# power.net
KiCad netlist of a schematic drawn in Altium Designer
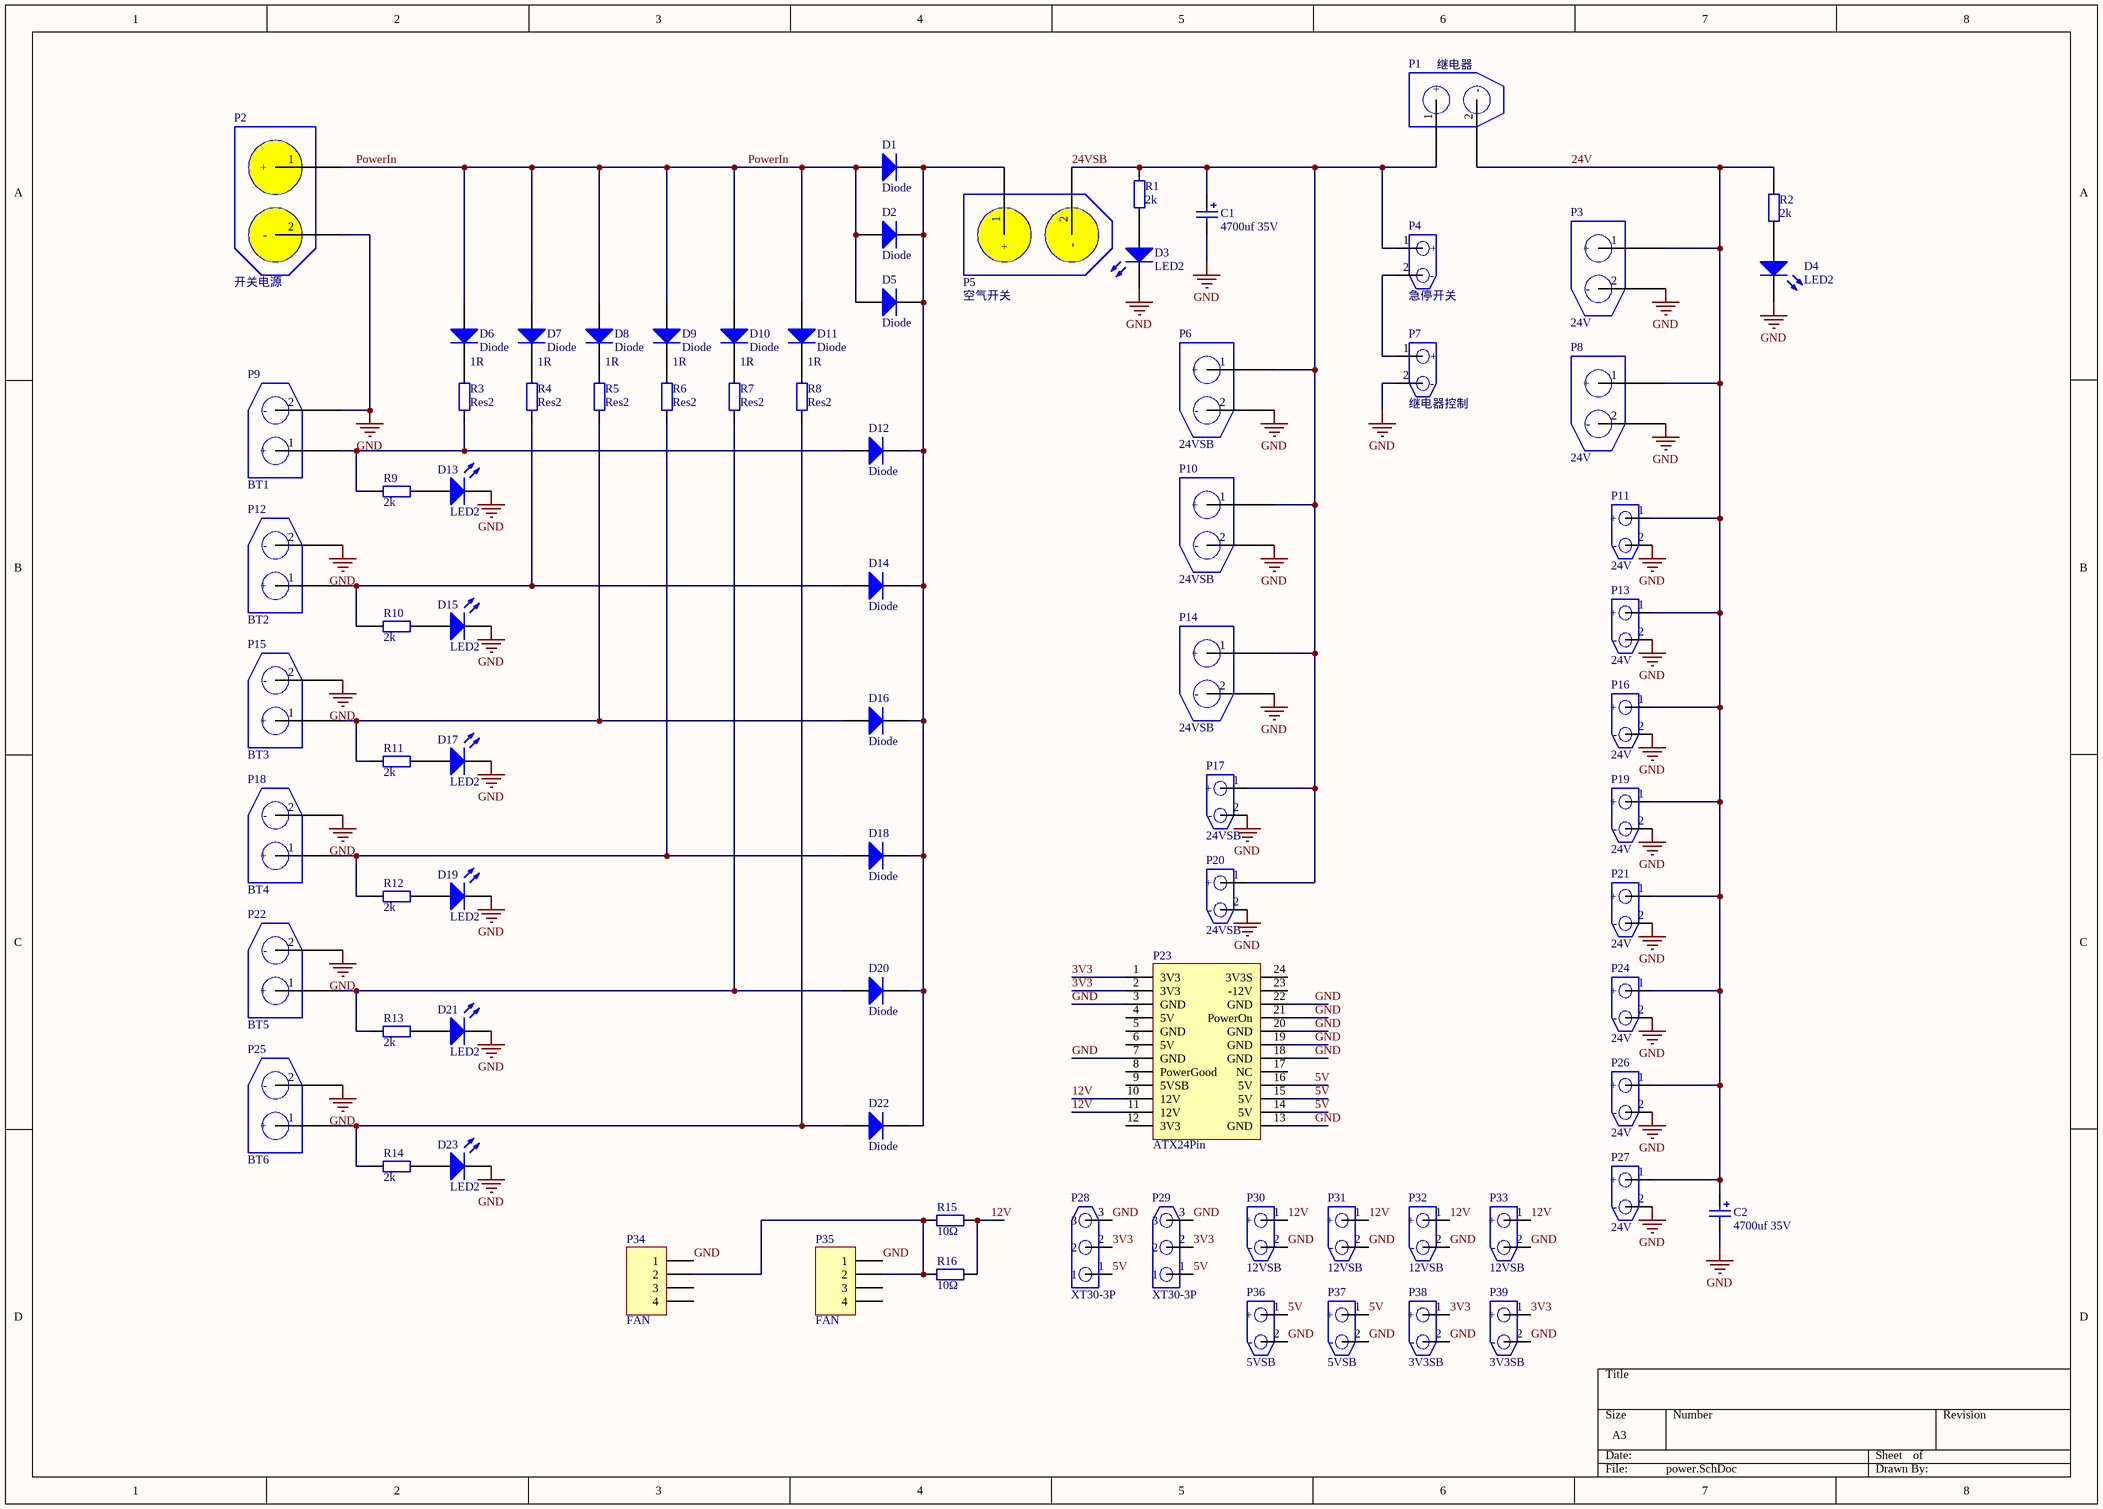
[diagram p0: power.SchDoc]

(export (version "E")
  (design (tool "Eeschema 10.0.6"))
  (components
    (comp (ref "C1")
      (value "4700uf 35V")
      (footprint "C1675")
      (description "Polarized Capacitor (Axial)")
      (fields (field (name "Comment") "Cap Pol2") (field (name "PUBLISHER") "Altium Limited"))
      (libsource (lib "Miscellaneous Devices") (part "Cap Pol2"))
    )
    (comp (ref "C2")
      (value "4700uf 35V")
      (footprint "C1675")
      (description "Polarized Capacitor (Axial)")
      (fields (field (name "Comment") "Cap Pol2") (field (name "PUBLISHER") "Altium Limited"))
      (libsource (lib "Miscellaneous Devices") (part "Cap Pol2"))
    )
    (comp (ref "D1")
      (value "Diode")
      (footprint "TO-247-2-S")
      (description "Default Diode")
      (fields (field (name "PUBLISHER") "Altium Limited"))
      (libsource (lib "Miscellaneous Devices") (part "Diode"))
    )
    (comp (ref "D2")
      (value "Diode")
      (footprint "TO-247-2-S")
      (description "Default Diode")
      (fields (field (name "PUBLISHER") "Altium Limited"))
      (libsource (lib "Miscellaneous Devices") (part "Diode"))
    )
    (comp (ref "D3")
      (value "LED2")
      (footprint "1608[0603]big")
      (description "Typical RED, GREEN, YELLOW, AMBER GaAs LED")
      (fields (field (name "PUBLISHER") "Altium Limited"))
      (libsource (lib "Miscellaneous Devices") (part "LED2"))
    )
    (comp (ref "D4")
      (value "LED2")
      (footprint "1608[0603]big")
      (description "Typical RED, GREEN, YELLOW, AMBER GaAs LED")
      (fields (field (name "PUBLISHER") "Altium Limited"))
      (libsource (lib "Miscellaneous Devices") (part "LED2"))
    )
    (comp (ref "D5")
      (value "Diode")
      (footprint "TO-247-2-S")
      (description "Default Diode")
      (fields (field (name "PUBLISHER") "Altium Limited"))
      (libsource (lib "Miscellaneous Devices") (part "Diode"))
    )
    (comp (ref "D6")
      (value "Diode")
      (footprint "TO-263")
      (description "Default Diode")
      (fields (field (name "PUBLISHER") "Altium Limited"))
      (libsource (lib "Miscellaneous Devices") (part "Diode"))
    )
    (comp (ref "D7")
      (value "Diode")
      (footprint "TO-263")
      (description "Default Diode")
      (fields (field (name "PUBLISHER") "Altium Limited"))
      (libsource (lib "Miscellaneous Devices") (part "Diode"))
    )
    (comp (ref "D8")
      (value "Diode")
      (footprint "TO-263")
      (description "Default Diode")
      (fields (field (name "PUBLISHER") "Altium Limited"))
      (libsource (lib "Miscellaneous Devices") (part "Diode"))
    )
    (comp (ref "D9")
      (value "Diode")
      (footprint "TO-263")
      (description "Default Diode")
      (fields (field (name "PUBLISHER") "Altium Limited"))
      (libsource (lib "Miscellaneous Devices") (part "Diode"))
    )
    (comp (ref "D10")
      (value "Diode")
      (footprint "TO-263")
      (description "Default Diode")
      (fields (field (name "PUBLISHER") "Altium Limited"))
      (libsource (lib "Miscellaneous Devices") (part "Diode"))
    )
    (comp (ref "D11")
      (value "Diode")
      (footprint "TO-263")
      (description "Default Diode")
      (fields (field (name "PUBLISHER") "Altium Limited"))
      (libsource (lib "Miscellaneous Devices") (part "Diode"))
    )
    (comp (ref "D12")
      (value "Diode")
      (footprint "TO-247-2-S")
      (description "Default Diode")
      (fields (field (name "PUBLISHER") "Altium Limited"))
      (libsource (lib "Miscellaneous Devices") (part "Diode"))
    )
    (comp (ref "D13")
      (value "LED2")
      (footprint "1608[0603]big")
      (description "Typical RED, GREEN, YELLOW, AMBER GaAs LED")
      (fields (field (name "PUBLISHER") "Altium Limited"))
      (libsource (lib "Miscellaneous Devices") (part "LED2"))
    )
    (comp (ref "D14")
      (value "Diode")
      (footprint "TO-247-2-S")
      (description "Default Diode")
      (fields (field (name "PUBLISHER") "Altium Limited"))
      (libsource (lib "Miscellaneous Devices") (part "Diode"))
    )
    (comp (ref "D15")
      (value "LED2")
      (footprint "1608[0603]big")
      (description "Typical RED, GREEN, YELLOW, AMBER GaAs LED")
      (fields (field (name "PUBLISHER") "Altium Limited"))
      (libsource (lib "Miscellaneous Devices") (part "LED2"))
    )
    (comp (ref "D16")
      (value "Diode")
      (footprint "TO-247-2-S")
      (description "Default Diode")
      (fields (field (name "PUBLISHER") "Altium Limited"))
      (libsource (lib "Miscellaneous Devices") (part "Diode"))
    )
    (comp (ref "D17")
      (value "LED2")
      (footprint "1608[0603]big")
      (description "Typical RED, GREEN, YELLOW, AMBER GaAs LED")
      (fields (field (name "PUBLISHER") "Altium Limited"))
      (libsource (lib "Miscellaneous Devices") (part "LED2"))
    )
    (comp (ref "D18")
      (value "Diode")
      (footprint "TO-247-2-S")
      (description "Default Diode")
      (fields (field (name "PUBLISHER") "Altium Limited"))
      (libsource (lib "Miscellaneous Devices") (part "Diode"))
    )
    (comp (ref "D19")
      (value "LED2")
      (footprint "1608[0603]big")
      (description "Typical RED, GREEN, YELLOW, AMBER GaAs LED")
      (fields (field (name "PUBLISHER") "Altium Limited"))
      (libsource (lib "Miscellaneous Devices") (part "LED2"))
    )
    (comp (ref "D20")
      (value "Diode")
      (footprint "TO-247-2-S")
      (description "Default Diode")
      (fields (field (name "PUBLISHER") "Altium Limited"))
      (libsource (lib "Miscellaneous Devices") (part "Diode"))
    )
    (comp (ref "D21")
      (value "LED2")
      (footprint "1608[0603]big")
      (description "Typical RED, GREEN, YELLOW, AMBER GaAs LED")
      (fields (field (name "PUBLISHER") "Altium Limited"))
      (libsource (lib "Miscellaneous Devices") (part "LED2"))
    )
    (comp (ref "D22")
      (value "Diode")
      (footprint "TO-247-2-S")
      (description "Default Diode")
      (fields (field (name "PUBLISHER") "Altium Limited"))
      (libsource (lib "Miscellaneous Devices") (part "Diode"))
    )
    (comp (ref "D23")
      (value "LED2")
      (footprint "1608[0603]big")
      (description "Typical RED, GREEN, YELLOW, AMBER GaAs LED")
      (fields (field (name "PUBLISHER") "Altium Limited"))
      (libsource (lib "Miscellaneous Devices") (part "LED2"))
    )
    (comp (ref "P1")
      (value "继电器")
      (footprint "XT60")
      (description "XT60")
      (libsource (lib "Schlib1") (part "XT60"))
    )
    (comp (ref "P2")
      (value "开关电源")
      (footprint "EC5-WIRE")
      (description "XT150")
      (libsource (lib "Schlib1") (part "XT150"))
    )
    (comp (ref "P3")
      (value "24V")
      (footprint "XT60")
      (description "XT60")
      (libsource (lib "Schlib1") (part "XT60"))
    )
    (comp (ref "P4")
      (value "急停开关")
      (footprint "XT30PCB")
      (description "XT30")
      (libsource (lib "Schlib1") (part "XT30"))
    )
    (comp (ref "P5")
      (value "空气开关")
      (footprint "EC5-WIRE")
      (description "XT150")
      (libsource (lib "Schlib1") (part "XT150"))
    )
    (comp (ref "P6")
      (value "24VSB")
      (footprint "XT60")
      (description "XT60")
      (libsource (lib "Schlib1") (part "XT60"))
    )
    (comp (ref "P7")
      (value "继电器控制")
      (footprint "XT30PCB")
      (description "XT30")
      (libsource (lib "Schlib1") (part "XT30"))
    )
    (comp (ref "P8")
      (value "24V")
      (footprint "XT60")
      (description "XT60")
      (libsource (lib "Schlib1") (part "XT60"))
    )
    (comp (ref "P9")
      (value "BT1")
      (footprint "XT60")
      (description "XT60")
      (libsource (lib "Schlib1") (part "XT60"))
    )
    (comp (ref "P10")
      (value "24VSB")
      (footprint "XT60")
      (description "XT60")
      (libsource (lib "Schlib1") (part "XT60"))
    )
    (comp (ref "P11")
      (value "24V")
      (footprint "XT30PCB")
      (description "XT30")
      (libsource (lib "Schlib1") (part "XT30"))
    )
    (comp (ref "P12")
      (value "BT2")
      (footprint "XT60")
      (description "XT60")
      (libsource (lib "Schlib1") (part "XT60"))
    )
    (comp (ref "P13")
      (value "24V")
      (footprint "XT30PCB")
      (description "XT30")
      (libsource (lib "Schlib1") (part "XT30"))
    )
    (comp (ref "P14")
      (value "24VSB")
      (footprint "XT60")
      (description "XT60")
      (libsource (lib "Schlib1") (part "XT60"))
    )
    (comp (ref "P15")
      (value "BT3")
      (footprint "XT60")
      (description "XT60")
      (libsource (lib "Schlib1") (part "XT60"))
    )
    (comp (ref "P16")
      (value "24V")
      (footprint "XT30PCB")
      (description "XT30")
      (libsource (lib "Schlib1") (part "XT30"))
    )
    (comp (ref "P17")
      (value "24VSB")
      (footprint "XT30PCB")
      (description "XT30")
      (libsource (lib "Schlib1") (part "XT30"))
    )
    (comp (ref "P18")
      (value "BT4")
      (footprint "XT60")
      (description "XT60")
      (libsource (lib "Schlib1") (part "XT60"))
    )
    (comp (ref "P19")
      (value "24V")
      (footprint "XT30PCB")
      (description "XT30")
      (libsource (lib "Schlib1") (part "XT30"))
    )
    (comp (ref "P20")
      (value "24VSB")
      (footprint "XT30PCB")
      (description "XT30")
      (libsource (lib "Schlib1") (part "XT30"))
    )
    (comp (ref "P21")
      (value "24V")
      (footprint "XT30PCB")
      (description "XT30")
      (libsource (lib "Schlib1") (part "XT30"))
    )
    (comp (ref "P22")
      (value "BT5")
      (footprint "XT60")
      (description "XT60")
      (libsource (lib "Schlib1") (part "XT60"))
    )
    (comp (ref "P23") (value "ATX24Pin") (footprint "ATX24P") (libsource (lib "Schlib1") (part "ATX24P")))
    (comp (ref "P24")
      (value "24V")
      (footprint "XT30PCB")
      (description "XT30")
      (libsource (lib "Schlib1") (part "XT30"))
    )
    (comp (ref "P25")
      (value "BT6")
      (footprint "XT60")
      (description "XT60")
      (libsource (lib "Schlib1") (part "XT60"))
    )
    (comp (ref "P26")
      (value "24V")
      (footprint "XT30PCB")
      (description "XT30")
      (libsource (lib "Schlib1") (part "XT30"))
    )
    (comp (ref "P27")
      (value "24V")
      (footprint "XT30PCB")
      (description "XT30")
      (libsource (lib "Schlib1") (part "XT30"))
    )
    (comp (ref "P28") (value "XT30-3P") (footprint "MR30PCB") (libsource (lib "Schlib1") (part "XT30-3P")))
    (comp (ref "P29") (value "XT30-3P") (footprint "MR30PCB") (libsource (lib "Schlib1") (part "XT30-3P")))
    (comp (ref "P30")
      (value "12VSB")
      (footprint "XT30PCB")
      (description "XT30")
      (libsource (lib "Schlib1") (part "XT30"))
    )
    (comp (ref "P31")
      (value "12VSB")
      (footprint "XT30PCB")
      (description "XT30")
      (libsource (lib "Schlib1") (part "XT30"))
    )
    (comp (ref "P32")
      (value "12VSB")
      (footprint "XT30PCB")
      (description "XT30")
      (libsource (lib "Schlib1") (part "XT30"))
    )
    (comp (ref "P33")
      (value "12VSB")
      (footprint "XT30PCB")
      (description "XT30")
      (libsource (lib "Schlib1") (part "XT30"))
    )
    (comp (ref "P34")
      (value "FAN")
      (footprint "HDR1X4")
      (description "Header, 4-Pin")
      (fields (field (name "PUBLISHER") "Altium Limited"))
      (libsource (lib "Miscellaneous Connectors") (part "Header 4"))
    )
    (comp (ref "P35")
      (value "FAN")
      (footprint "HDR1X4")
      (description "Header, 4-Pin")
      (fields (field (name "PUBLISHER") "Altium Limited"))
      (libsource (lib "Miscellaneous Connectors") (part "Header 4"))
    )
    (comp (ref "P36")
      (value "5VSB")
      (footprint "XT30PCB")
      (description "XT30")
      (libsource (lib "Schlib1") (part "XT30"))
    )
    (comp (ref "P37")
      (value "5VSB")
      (footprint "XT30PCB")
      (description "XT30")
      (libsource (lib "Schlib1") (part "XT30"))
    )
    (comp (ref "P38")
      (value "3V3SB")
      (footprint "XT30PCB")
      (description "XT30")
      (libsource (lib "Schlib1") (part "XT30"))
    )
    (comp (ref "P39")
      (value "3V3SB")
      (footprint "XT30PCB")
      (description "XT30")
      (libsource (lib "Schlib1") (part "XT30"))
    )
    (comp (ref "R1")
      (value "2k")
      (footprint "1608[0603]big")
      (description "Resistor")
      (fields (field (name "Comment") "Res2") (field (name "PUBLISHER") "Altium Limited"))
      (libsource (lib "Miscellaneous Devices") (part "Res2"))
    )
    (comp (ref "R2")
      (value "2k")
      (footprint "1608[0603]big")
      (description "Resistor")
      (fields (field (name "Comment") "Res2") (field (name "PUBLISHER") "Altium Limited"))
      (libsource (lib "Miscellaneous Devices") (part "Res2"))
    )
    (comp (ref "R3")
      (value "Res2")
      (footprint "RX24-30W")
      (description "Resistor")
      (fields (field (name "ALTIUM_VALUE") "1R") (field (name "PUBLISHER") "Altium Limited"))
      (libsource (lib "Miscellaneous Devices") (part "Res2"))
    )
    (comp (ref "R4")
      (value "Res2")
      (footprint "RX24-30W")
      (description "Resistor")
      (fields (field (name "ALTIUM_VALUE") "1R") (field (name "PUBLISHER") "Altium Limited"))
      (libsource (lib "Miscellaneous Devices") (part "Res2"))
    )
    (comp (ref "R5")
      (value "Res2")
      (footprint "RX24-30W")
      (description "Resistor")
      (fields (field (name "ALTIUM_VALUE") "1R") (field (name "PUBLISHER") "Altium Limited"))
      (libsource (lib "Miscellaneous Devices") (part "Res2"))
    )
    (comp (ref "R6")
      (value "Res2")
      (footprint "RX24-30W")
      (description "Resistor")
      (fields (field (name "ALTIUM_VALUE") "1R") (field (name "PUBLISHER") "Altium Limited"))
      (libsource (lib "Miscellaneous Devices") (part "Res2"))
    )
    (comp (ref "R7")
      (value "Res2")
      (footprint "RX24-30W")
      (description "Resistor")
      (fields (field (name "ALTIUM_VALUE") "1R") (field (name "PUBLISHER") "Altium Limited"))
      (libsource (lib "Miscellaneous Devices") (part "Res2"))
    )
    (comp (ref "R8")
      (value "Res2")
      (footprint "RX24-30W")
      (description "Resistor")
      (fields (field (name "ALTIUM_VALUE") "1R") (field (name "PUBLISHER") "Altium Limited"))
      (libsource (lib "Miscellaneous Devices") (part "Res2"))
    )
    (comp (ref "R9")
      (value "2k")
      (footprint "1608[0603]big")
      (description "Resistor")
      (fields (field (name "Comment") "Res2") (field (name "PUBLISHER") "Altium Limited"))
      (libsource (lib "") (part "Res2_1"))
    )
    (comp (ref "R10")
      (value "2k")
      (footprint "1608[0603]big")
      (description "Resistor")
      (fields (field (name "Comment") "Res2") (field (name "PUBLISHER") "Altium Limited"))
      (libsource (lib "") (part "Res2_1"))
    )
    (comp (ref "R11")
      (value "2k")
      (footprint "1608[0603]big")
      (description "Resistor")
      (fields (field (name "Comment") "Res2") (field (name "PUBLISHER") "Altium Limited"))
      (libsource (lib "") (part "Res2_1"))
    )
    (comp (ref "R12")
      (value "2k")
      (footprint "1608[0603]big")
      (description "Resistor")
      (fields (field (name "Comment") "Res2") (field (name "PUBLISHER") "Altium Limited"))
      (libsource (lib "") (part "Res2_1"))
    )
    (comp (ref "R13")
      (value "2k")
      (footprint "1608[0603]big")
      (description "Resistor")
      (fields (field (name "Comment") "Res2") (field (name "PUBLISHER") "Altium Limited"))
      (libsource (lib "") (part "Res2_1"))
    )
    (comp (ref "R14")
      (value "2k")
      (footprint "1608[0603]big")
      (description "Resistor")
      (fields (field (name "Comment") "Res2") (field (name "PUBLISHER") "Altium Limited"))
      (libsource (lib "") (part "Res2_1"))
    )
    (comp (ref "R15")
      (value "10Ω")
      (footprint "SMC")
      (description "Resistor")
      (fields (field (name "Comment") "Res2") (field (name "PUBLISHER") "Altium Limited"))
      (libsource (lib "") (part "Res2_1"))
    )
    (comp (ref "R16")
      (value "10Ω")
      (footprint "SMC")
      (description "Resistor")
      (fields (field (name "Comment") "Res2") (field (name "PUBLISHER") "Altium Limited"))
      (libsource (lib "") (part "Res2_1"))
    )
  )
  (nets
    (net (code "1") (name "/3V3") (class "Default")
      (node (ref "P23") (pin "1") (pinfunction "3V3_1") (pintype "passive"))
      (node (ref "P23") (pin "2") (pinfunction "3V3_2") (pintype "passive"))
      (node (ref "P28") (pin "2") (pinfunction "2_2") (pintype "passive"))
      (node (ref "P29") (pin "2") (pinfunction "2_2") (pintype "passive"))
      (node (ref "P38") (pin "1") (pinfunction "+_1") (pintype "passive"))
      (node (ref "P39") (pin "1") (pinfunction "+_1") (pintype "passive"))
    )
    (net (code "2") (name "/5V") (class "Default")
      (node (ref "P23") (pin "14") (pinfunction "5V_14") (pintype "passive"))
      (node (ref "P23") (pin "15") (pinfunction "5V_15") (pintype "passive"))
      (node (ref "P23") (pin "16") (pinfunction "5V_16") (pintype "passive"))
      (node (ref "P28") (pin "1") (pinfunction "1_1") (pintype "passive"))
      (node (ref "P29") (pin "1") (pinfunction "1_1") (pintype "passive"))
      (node (ref "P36") (pin "1") (pinfunction "+_1") (pintype "passive"))
      (node (ref "P37") (pin "1") (pinfunction "+_1") (pintype "passive"))
    )
    (net (code "3") (name "/12V") (class "Default")
      (node (ref "P23") (pin "10") (pinfunction "12V_10") (pintype "passive"))
      (node (ref "P23") (pin "11") (pinfunction "12V_11") (pintype "passive"))
      (node (ref "P30") (pin "1") (pinfunction "+_1") (pintype "passive"))
      (node (ref "P31") (pin "1") (pinfunction "+_1") (pintype "passive"))
      (node (ref "P32") (pin "1") (pinfunction "+_1") (pintype "passive"))
      (node (ref "P33") (pin "1") (pinfunction "+_1") (pintype "passive"))
      (node (ref "R15") (pin "1") (pinfunction "1_1") (pintype "passive"))
      (node (ref "R16") (pin "1") (pinfunction "1_1") (pintype "passive"))
    )
    (net (code "4") (name "/24V") (class "Default")
      (node (ref "C2") (pin "1") (pinfunction "1_1") (pintype "passive"))
      (node (ref "P1") (pin "2") (pinfunction "-_2") (pintype "passive"))
      (node (ref "P11") (pin "1") (pinfunction "+_1") (pintype "passive"))
      (node (ref "P13") (pin "1") (pinfunction "+_1") (pintype "passive"))
      (node (ref "P16") (pin "1") (pinfunction "+_1") (pintype "passive"))
      (node (ref "P19") (pin "1") (pinfunction "+_1") (pintype "passive"))
      (node (ref "P21") (pin "1") (pinfunction "+_1") (pintype "passive"))
      (node (ref "P24") (pin "1") (pinfunction "+_1") (pintype "passive"))
      (node (ref "P26") (pin "1") (pinfunction "+_1") (pintype "passive"))
      (node (ref "P27") (pin "1") (pinfunction "+_1") (pintype "passive"))
      (node (ref "P3") (pin "1") (pinfunction "+_1") (pintype "passive"))
      (node (ref "P8") (pin "1") (pinfunction "+_1") (pintype "passive"))
      (node (ref "R2") (pin "2") (pinfunction "2_2") (pintype "passive"))
    )
    (net (code "5") (name "/24VSB") (class "Default")
      (node (ref "C1") (pin "1") (pinfunction "1_1") (pintype "passive"))
      (node (ref "P1") (pin "1") (pinfunction "+_1") (pintype "passive"))
      (node (ref "P10") (pin "1") (pinfunction "+_1") (pintype "passive"))
      (node (ref "P14") (pin "1") (pinfunction "+_1") (pintype "passive"))
      (node (ref "P17") (pin "1") (pinfunction "+_1") (pintype "passive"))
      (node (ref "P20") (pin "1") (pinfunction "+_1") (pintype "passive"))
      (node (ref "P4") (pin "1") (pinfunction "+_1") (pintype "passive"))
      (node (ref "P5") (pin "2") (pinfunction "-_2") (pintype "passive"))
      (node (ref "P6") (pin "1") (pinfunction "+_1") (pintype "passive"))
      (node (ref "R1") (pin "2") (pinfunction "2_2") (pintype "passive"))
    )
    (net (code "6") (name "/PowerIn") (class "Default")
      (node (ref "D1") (pin "1") (pinfunction "A_1") (pintype "passive"))
      (node (ref "D10") (pin "1") (pinfunction "A_1") (pintype "passive"))
      (node (ref "D11") (pin "1") (pinfunction "A_1") (pintype "passive"))
      (node (ref "D2") (pin "1") (pinfunction "A_1") (pintype "passive"))
      (node (ref "D5") (pin "1") (pinfunction "A_1") (pintype "passive"))
      (node (ref "D6") (pin "1") (pinfunction "A_1") (pintype "passive"))
      (node (ref "D7") (pin "1") (pinfunction "A_1") (pintype "passive"))
      (node (ref "D8") (pin "1") (pinfunction "A_1") (pintype "passive"))
      (node (ref "D9") (pin "1") (pinfunction "A_1") (pintype "passive"))
      (node (ref "P2") (pin "1") (pinfunction "+_1") (pintype "passive"))
    )
    (net (code "7") (name "GND") (class "Default")
      (node (ref "C1") (pin "2") (pinfunction "2_2") (pintype "passive"))
      (node (ref "C2") (pin "2") (pinfunction "2_2") (pintype "passive"))
      (node (ref "D13") (pin "2") (pinfunction "K_2") (pintype "passive"))
      (node (ref "D15") (pin "2") (pinfunction "K_2") (pintype "passive"))
      (node (ref "D17") (pin "2") (pinfunction "K_2") (pintype "passive"))
      (node (ref "D19") (pin "2") (pinfunction "K_2") (pintype "passive"))
      (node (ref "D21") (pin "2") (pinfunction "K_2") (pintype "passive"))
      (node (ref "D23") (pin "2") (pinfunction "K_2") (pintype "passive"))
      (node (ref "D3") (pin "2") (pinfunction "K_2") (pintype "passive"))
      (node (ref "D4") (pin "2") (pinfunction "K_2") (pintype "passive"))
      (node (ref "P10") (pin "2") (pinfunction "-_2") (pintype "passive"))
      (node (ref "P11") (pin "2") (pinfunction "-_2") (pintype "passive"))
      (node (ref "P12") (pin "2") (pinfunction "-_2") (pintype "passive"))
      (node (ref "P13") (pin "2") (pinfunction "-_2") (pintype "passive"))
      (node (ref "P14") (pin "2") (pinfunction "-_2") (pintype "passive"))
      (node (ref "P15") (pin "2") (pinfunction "-_2") (pintype "passive"))
      (node (ref "P16") (pin "2") (pinfunction "-_2") (pintype "passive"))
      (node (ref "P17") (pin "2") (pinfunction "-_2") (pintype "passive"))
      (node (ref "P18") (pin "2") (pinfunction "-_2") (pintype "passive"))
      (node (ref "P19") (pin "2") (pinfunction "-_2") (pintype "passive"))
      (node (ref "P2") (pin "2") (pinfunction "-_2") (pintype "passive"))
      (node (ref "P20") (pin "2") (pinfunction "-_2") (pintype "passive"))
      (node (ref "P21") (pin "2") (pinfunction "-_2") (pintype "passive"))
      (node (ref "P22") (pin "2") (pinfunction "-_2") (pintype "passive"))
      (node (ref "P23") (pin "13") (pinfunction "GND_13") (pintype "passive"))
      (node (ref "P23") (pin "18") (pinfunction "GND_18") (pintype "passive"))
      (node (ref "P23") (pin "19") (pinfunction "GND_19") (pintype "passive"))
      (node (ref "P23") (pin "20") (pinfunction "GND_20") (pintype "passive"))
      (node (ref "P23") (pin "21") (pinfunction "PowerOn_21") (pintype "passive"))
      (node (ref "P23") (pin "22") (pinfunction "GND_22") (pintype "passive"))
      (node (ref "P23") (pin "3") (pinfunction "GND_3") (pintype "passive"))
      (node (ref "P23") (pin "7") (pinfunction "GND_7") (pintype "passive"))
      (node (ref "P24") (pin "2") (pinfunction "-_2") (pintype "passive"))
      (node (ref "P25") (pin "2") (pinfunction "-_2") (pintype "passive"))
      (node (ref "P26") (pin "2") (pinfunction "-_2") (pintype "passive"))
      (node (ref "P27") (pin "2") (pinfunction "-_2") (pintype "passive"))
      (node (ref "P28") (pin "3") (pinfunction "3_3") (pintype "passive"))
      (node (ref "P29") (pin "3") (pinfunction "3_3") (pintype "passive"))
      (node (ref "P3") (pin "2") (pinfunction "-_2") (pintype "passive"))
      (node (ref "P30") (pin "2") (pinfunction "-_2") (pintype "passive"))
      (node (ref "P31") (pin "2") (pinfunction "-_2") (pintype "passive"))
      (node (ref "P32") (pin "2") (pinfunction "-_2") (pintype "passive"))
      (node (ref "P33") (pin "2") (pinfunction "-_2") (pintype "passive"))
      (node (ref "P34") (pin "1") (pinfunction "1_1") (pintype "passive"))
      (node (ref "P35") (pin "1") (pinfunction "1_1") (pintype "passive"))
      (node (ref "P36") (pin "2") (pinfunction "-_2") (pintype "passive"))
      (node (ref "P37") (pin "2") (pinfunction "-_2") (pintype "passive"))
      (node (ref "P38") (pin "2") (pinfunction "-_2") (pintype "passive"))
      (node (ref "P39") (pin "2") (pinfunction "-_2") (pintype "passive"))
      (node (ref "P6") (pin "2") (pinfunction "-_2") (pintype "passive"))
      (node (ref "P7") (pin "2") (pinfunction "-_2") (pintype "passive"))
      (node (ref "P8") (pin "2") (pinfunction "-_2") (pintype "passive"))
      (node (ref "P9") (pin "2") (pinfunction "-_2") (pintype "passive"))
    )
    (net (code "8") (name "Net-(D1-K)") (class "Default")
      (node (ref "D1") (pin "2") (pinfunction "K_2") (pintype "passive"))
      (node (ref "D12") (pin "2") (pinfunction "K_2") (pintype "passive"))
      (node (ref "D14") (pin "2") (pinfunction "K_2") (pintype "passive"))
      (node (ref "D16") (pin "2") (pinfunction "K_2") (pintype "passive"))
      (node (ref "D18") (pin "2") (pinfunction "K_2") (pintype "passive"))
      (node (ref "D2") (pin "2") (pinfunction "K_2") (pintype "passive"))
      (node (ref "D20") (pin "2") (pinfunction "K_2") (pintype "passive"))
      (node (ref "D22") (pin "2") (pinfunction "K_2") (pintype "passive"))
      (node (ref "D5") (pin "2") (pinfunction "K_2") (pintype "passive"))
      (node (ref "P5") (pin "1") (pinfunction "+_1") (pintype "passive"))
    )
    (net (code "9") (name "Net-(D3-A)") (class "Default")
      (node (ref "D3") (pin "1") (pinfunction "A_1") (pintype "passive"))
      (node (ref "R1") (pin "1") (pinfunction "1_1") (pintype "passive"))
    )
    (net (code "10") (name "Net-(D4-A)") (class "Default")
      (node (ref "D4") (pin "1") (pinfunction "A_1") (pintype "passive"))
      (node (ref "R2") (pin "1") (pinfunction "1_1") (pintype "passive"))
    )
    (net (code "11") (name "Net-(D6-K)") (class "Default")
      (node (ref "D6") (pin "2") (pinfunction "K_2") (pintype "passive"))
      (node (ref "R3") (pin "2") (pinfunction "2_2") (pintype "passive"))
    )
    (net (code "12") (name "Net-(D7-K)") (class "Default")
      (node (ref "D7") (pin "2") (pinfunction "K_2") (pintype "passive"))
      (node (ref "R4") (pin "2") (pinfunction "2_2") (pintype "passive"))
    )
    (net (code "13") (name "Net-(D8-K)") (class "Default")
      (node (ref "D8") (pin "2") (pinfunction "K_2") (pintype "passive"))
      (node (ref "R5") (pin "2") (pinfunction "2_2") (pintype "passive"))
    )
    (net (code "14") (name "Net-(D9-K)") (class "Default")
      (node (ref "D9") (pin "2") (pinfunction "K_2") (pintype "passive"))
      (node (ref "R6") (pin "2") (pinfunction "2_2") (pintype "passive"))
    )
    (net (code "15") (name "Net-(D10-K)") (class "Default")
      (node (ref "D10") (pin "2") (pinfunction "K_2") (pintype "passive"))
      (node (ref "R7") (pin "2") (pinfunction "2_2") (pintype "passive"))
    )
    (net (code "16") (name "Net-(D11-K)") (class "Default")
      (node (ref "D11") (pin "2") (pinfunction "K_2") (pintype "passive"))
      (node (ref "R8") (pin "2") (pinfunction "2_2") (pintype "passive"))
    )
    (net (code "17") (name "Net-(D12-A)") (class "Default")
      (node (ref "D12") (pin "1") (pinfunction "A_1") (pintype "passive"))
      (node (ref "P9") (pin "1") (pinfunction "+_1") (pintype "passive"))
      (node (ref "R3") (pin "1") (pinfunction "1_1") (pintype "passive"))
      (node (ref "R9") (pin "2") (pinfunction "2_2") (pintype "passive"))
    )
    (net (code "18") (name "Net-(D13-A)") (class "Default")
      (node (ref "D13") (pin "1") (pinfunction "A_1") (pintype "passive"))
      (node (ref "R9") (pin "1") (pinfunction "1_1") (pintype "passive"))
    )
    (net (code "19") (name "Net-(D14-A)") (class "Default")
      (node (ref "D14") (pin "1") (pinfunction "A_1") (pintype "passive"))
      (node (ref "P12") (pin "1") (pinfunction "+_1") (pintype "passive"))
      (node (ref "R10") (pin "2") (pinfunction "2_2") (pintype "passive"))
      (node (ref "R4") (pin "1") (pinfunction "1_1") (pintype "passive"))
    )
    (net (code "20") (name "Net-(D15-A)") (class "Default")
      (node (ref "D15") (pin "1") (pinfunction "A_1") (pintype "passive"))
      (node (ref "R10") (pin "1") (pinfunction "1_1") (pintype "passive"))
    )
    (net (code "21") (name "Net-(D16-A)") (class "Default")
      (node (ref "D16") (pin "1") (pinfunction "A_1") (pintype "passive"))
      (node (ref "P15") (pin "1") (pinfunction "+_1") (pintype "passive"))
      (node (ref "R11") (pin "2") (pinfunction "2_2") (pintype "passive"))
      (node (ref "R5") (pin "1") (pinfunction "1_1") (pintype "passive"))
    )
    (net (code "22") (name "Net-(D17-A)") (class "Default")
      (node (ref "D17") (pin "1") (pinfunction "A_1") (pintype "passive"))
      (node (ref "R11") (pin "1") (pinfunction "1_1") (pintype "passive"))
    )
    (net (code "23") (name "Net-(D18-A)") (class "Default")
      (node (ref "D18") (pin "1") (pinfunction "A_1") (pintype "passive"))
      (node (ref "P18") (pin "1") (pinfunction "+_1") (pintype "passive"))
      (node (ref "R12") (pin "2") (pinfunction "2_2") (pintype "passive"))
      (node (ref "R6") (pin "1") (pinfunction "1_1") (pintype "passive"))
    )
    (net (code "24") (name "Net-(D19-A)") (class "Default")
      (node (ref "D19") (pin "1") (pinfunction "A_1") (pintype "passive"))
      (node (ref "R12") (pin "1") (pinfunction "1_1") (pintype "passive"))
    )
    (net (code "25") (name "Net-(D20-A)") (class "Default")
      (node (ref "D20") (pin "1") (pinfunction "A_1") (pintype "passive"))
      (node (ref "P22") (pin "1") (pinfunction "+_1") (pintype "passive"))
      (node (ref "R13") (pin "2") (pinfunction "2_2") (pintype "passive"))
      (node (ref "R7") (pin "1") (pinfunction "1_1") (pintype "passive"))
    )
    (net (code "26") (name "Net-(D21-A)") (class "Default")
      (node (ref "D21") (pin "1") (pinfunction "A_1") (pintype "passive"))
      (node (ref "R13") (pin "1") (pinfunction "1_1") (pintype "passive"))
    )
    (net (code "27") (name "Net-(D22-A)") (class "Default")
      (node (ref "D22") (pin "1") (pinfunction "A_1") (pintype "passive"))
      (node (ref "P25") (pin "1") (pinfunction "+_1") (pintype "passive"))
      (node (ref "R14") (pin "2") (pinfunction "2_2") (pintype "passive"))
      (node (ref "R8") (pin "1") (pinfunction "1_1") (pintype "passive"))
    )
    (net (code "28") (name "Net-(D23-A)") (class "Default")
      (node (ref "D23") (pin "1") (pinfunction "A_1") (pintype "passive"))
      (node (ref "R14") (pin "1") (pinfunction "1_1") (pintype "passive"))
    )
    (net (code "29") (name "Net-(P4--)") (class "Default")
      (node (ref "P4") (pin "2") (pinfunction "-_2") (pintype "passive"))
      (node (ref "P7") (pin "1") (pinfunction "+_1") (pintype "passive"))
    )
    (net (code "30") (name "Net-(P34-Pad2)") (class "Default")
      (node (ref "P34") (pin "2") (pinfunction "2_2") (pintype "passive"))
      (node (ref "P35") (pin "2") (pinfunction "2_2") (pintype "passive"))
      (node (ref "R15") (pin "2") (pinfunction "2_2") (pintype "passive"))
      (node (ref "R16") (pin "2") (pinfunction "2_2") (pintype "passive"))
    )
    (net (code "31") (name "unconnected-(P23--12V-Pad23)") (class "Default")
      (node (ref "P23") (pin "23") (pinfunction "-12V_23") (pintype "passive"))
    )
    (net (code "32") (name "unconnected-(P23-3V3-Pad12)") (class "Default")
      (node (ref "P23") (pin "12") (pinfunction "3V3_12") (pintype "passive"))
    )
    (net (code "33") (name "unconnected-(P23-3V3S-Pad24)") (class "Default")
      (node (ref "P23") (pin "24") (pinfunction "3V3S_24") (pintype "passive"))
    )
    (net (code "34") (name "unconnected-(P23-5V-Pad4)") (class "Default")
      (node (ref "P23") (pin "4") (pinfunction "5V_4") (pintype "passive"))
    )
    (net (code "35") (name "unconnected-(P23-5V-Pad6)") (class "Default")
      (node (ref "P23") (pin "6") (pinfunction "5V_6") (pintype "passive"))
    )
    (net (code "36") (name "unconnected-(P23-5VSB-Pad9)") (class "Default")
      (node (ref "P23") (pin "9") (pinfunction "5VSB_9") (pintype "passive"))
    )
    (net (code "37") (name "unconnected-(P23-GND-Pad5)") (class "Default")
      (node (ref "P23") (pin "5") (pinfunction "GND_5") (pintype "passive"))
    )
    (net (code "38") (name "unconnected-(P23-NC-Pad17)") (class "Default")
      (node (ref "P23") (pin "17") (pinfunction "NC_17") (pintype "passive"))
    )
    (net (code "39") (name "unconnected-(P23-PowerGood-Pad8)") (class "Default")
      (node (ref "P23") (pin "8") (pinfunction "PowerGood_8") (pintype "passive"))
    )
    (net (code "40") (name "unconnected-(P34-Pad3)") (class "Default")
      (node (ref "P34") (pin "3") (pinfunction "3_3") (pintype "passive"))
    )
    (net (code "41") (name "unconnected-(P34-Pad4)") (class "Default")
      (node (ref "P34") (pin "4") (pinfunction "4_4") (pintype "passive"))
    )
    (net (code "42") (name "unconnected-(P35-Pad3)") (class "Default")
      (node (ref "P35") (pin "3") (pinfunction "3_3") (pintype "passive"))
    )
    (net (code "43") (name "unconnected-(P35-Pad4)") (class "Default")
      (node (ref "P35") (pin "4") (pinfunction "4_4") (pintype "passive"))
    )
  )
)
